# led_pack12.net
KiCad netlist of a schematic drawn in Altium Designer
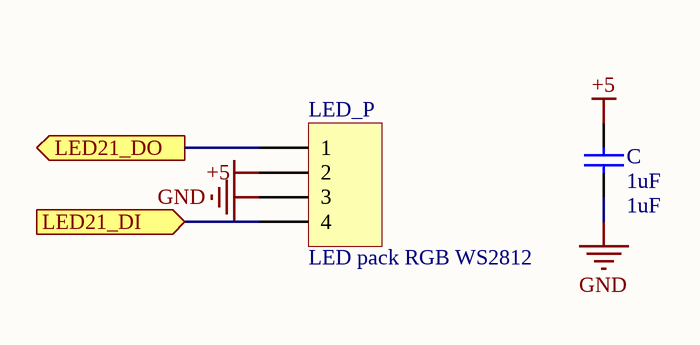
[diagram p0: led_pack12.SchDoc]

(export (version "E")
  (design (tool "Eeschema 10.0.6"))
  (components
    (comp (ref "C")
      (value "1uF")
      (footprint "0603C")
      (description "CAP SMD 0603")
      (fields (field (name "ALTIUM_VALUE") "1uF") (field (name "PUBLISHER") "Altium Limited"))
      (libsource (lib "Miscellaneous Devices") (part "Cap"))
    )
    (comp (ref "LED_P")
      (value "LED pack RGB WS2812")
      (footprint "pack21-2121")
      (description "5 RGB LED pack")
      (fields (field (name "PUBLISHER") "Altium Limited"))
      (libsource (lib "Altium") (part "Header 4"))
    )
  )
  (nets
    (net (code "1") (name "+5") (class "Default")
      (node (ref "C") (pin "2") (pinfunction "2_2") (pintype "passive"))
      (node (ref "LED_P") (pin "2") (pinfunction "2_2") (pintype "passive"))
    )
    (net (code "2") (name "/LED21_DI") (class "Default")
      (node (ref "LED_P") (pin "4") (pinfunction "4_4") (pintype "passive"))
    )
    (net (code "3") (name "/LED21_DO") (class "Default")
      (node (ref "LED_P") (pin "1") (pinfunction "1_1") (pintype "passive"))
    )
    (net (code "4") (name "GND") (class "Default")
      (node (ref "C") (pin "1") (pinfunction "1_1") (pintype "passive"))
      (node (ref "LED_P") (pin "3") (pinfunction "3_3") (pintype "passive"))
    )
  )
)
